# heimdall5.net
KiCad netlist of a schematic drawn in EAGLE
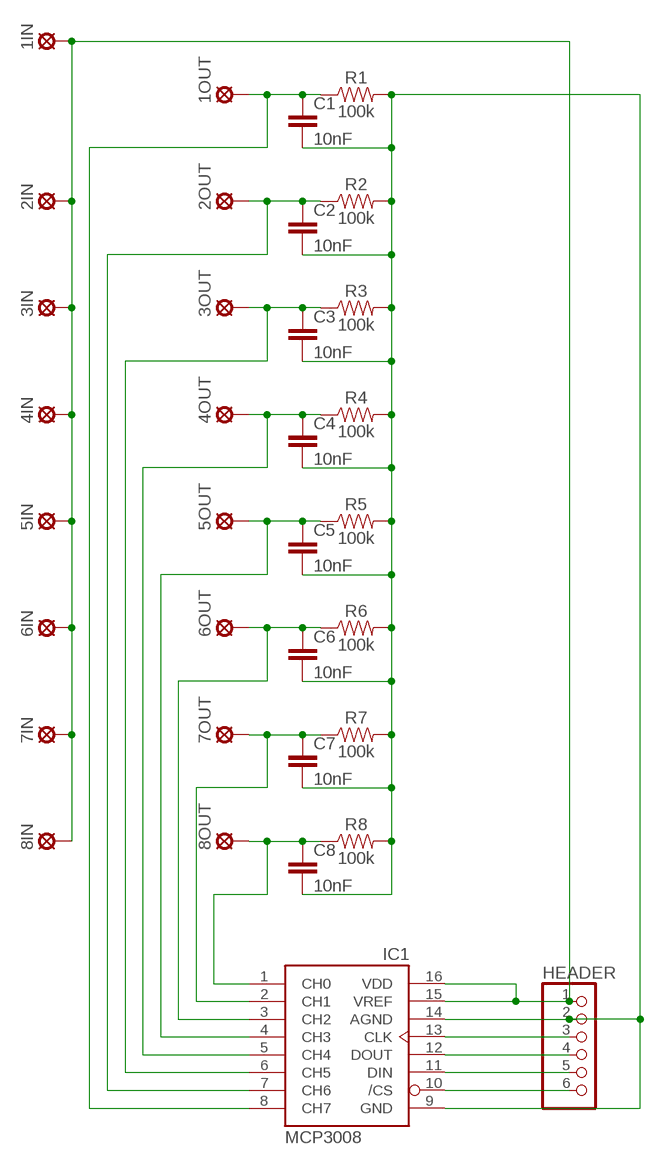
[diagram p0: schematic, sheet 1]

(export (version "E")
  (design (tool "Eeschema 10.0.6"))
  (components
    (comp (ref "1IN")
      (value "LSP11")
      (footprint "eagle-import:LSP11")
      (libsource (lib "eagle-import") (part "LSP11"))
    )
    (comp (ref "1OUT")
      (value "LSP11")
      (footprint "eagle-import:LSP11")
      (libsource (lib "eagle-import") (part "LSP11"))
    )
    (comp (ref "2IN")
      (value "LSP11")
      (footprint "eagle-import:LSP11")
      (libsource (lib "eagle-import") (part "LSP11"))
    )
    (comp (ref "2OUT")
      (value "LSP11")
      (footprint "eagle-import:LSP11")
      (libsource (lib "eagle-import") (part "LSP11"))
    )
    (comp (ref "3IN")
      (value "LSP11")
      (footprint "eagle-import:LSP11")
      (libsource (lib "eagle-import") (part "LSP11"))
    )
    (comp (ref "3OUT")
      (value "LSP11")
      (footprint "eagle-import:LSP11")
      (libsource (lib "eagle-import") (part "LSP11"))
    )
    (comp (ref "4IN")
      (value "LSP11")
      (footprint "eagle-import:LSP11")
      (libsource (lib "eagle-import") (part "LSP11"))
    )
    (comp (ref "4OUT")
      (value "LSP11")
      (footprint "eagle-import:LSP11")
      (libsource (lib "eagle-import") (part "LSP11"))
    )
    (comp (ref "5IN")
      (value "LSP11")
      (footprint "eagle-import:LSP11")
      (libsource (lib "eagle-import") (part "LSP11"))
    )
    (comp (ref "5OUT")
      (value "LSP11")
      (footprint "eagle-import:LSP11")
      (libsource (lib "eagle-import") (part "LSP11"))
    )
    (comp (ref "6IN")
      (value "LSP11")
      (footprint "eagle-import:LSP11")
      (libsource (lib "eagle-import") (part "LSP11"))
    )
    (comp (ref "6OUT")
      (value "LSP11")
      (footprint "eagle-import:LSP11")
      (libsource (lib "eagle-import") (part "LSP11"))
    )
    (comp (ref "7IN")
      (value "LSP11")
      (footprint "eagle-import:LSP11")
      (libsource (lib "eagle-import") (part "LSP11"))
    )
    (comp (ref "7OUT")
      (value "LSP11")
      (footprint "eagle-import:LSP11")
      (libsource (lib "eagle-import") (part "LSP11"))
    )
    (comp (ref "8IN")
      (value "LSP11")
      (footprint "eagle-import:LSP11")
      (libsource (lib "eagle-import") (part "LSP11"))
    )
    (comp (ref "8OUT")
      (value "LSP11")
      (footprint "eagle-import:LSP11")
      (libsource (lib "eagle-import") (part "LSP11"))
    )
    (comp (ref "C1")
      (value "10nF")
      (footprint "eagle-import:050X030_050")
      (libsource (lib "eagle-import") (part "050X030_0502"))
    )
    (comp (ref "C2")
      (value "10nF")
      (footprint "eagle-import:050X030_050")
      (libsource (lib "eagle-import") (part "050X030_0502"))
    )
    (comp (ref "C3")
      (value "10nF")
      (footprint "eagle-import:050X030_050")
      (libsource (lib "eagle-import") (part "050X030_0502"))
    )
    (comp (ref "C4")
      (value "10nF")
      (footprint "eagle-import:050X030_050")
      (libsource (lib "eagle-import") (part "050X030_0502"))
    )
    (comp (ref "C5")
      (value "10nF")
      (footprint "eagle-import:050X030_050")
      (libsource (lib "eagle-import") (part "050X030_0502"))
    )
    (comp (ref "C6")
      (value "10nF")
      (footprint "eagle-import:050X030_050")
      (libsource (lib "eagle-import") (part "050X030_0502"))
    )
    (comp (ref "C7")
      (value "10nF")
      (footprint "eagle-import:050X030_050")
      (libsource (lib "eagle-import") (part "050X030_0502"))
    )
    (comp (ref "C8")
      (value "10nF")
      (footprint "eagle-import:050X030_050")
      (libsource (lib "eagle-import") (part "050X030_0502"))
    )
    (comp (ref "HEADER")
      (value "PINHD-1X6")
      (footprint "eagle-import:1X06")
      (libsource (lib "eagle-import") (part "PINHD-1X6"))
    )
    (comp (ref "IC1")
      (value "MCP3008")
      (footprint "eagle-import:DIL16")
      (libsource (lib "eagle-import") (part "MCP3008"))
    )
    (comp (ref "R1")
      (value "100k")
      (footprint "eagle-import:AXIAL-0.3")
      (libsource (lib "eagle-import") (part "100KOHM-HORIZ-1/4W-1%"))
    )
    (comp (ref "R2")
      (value "100k")
      (footprint "eagle-import:AXIAL-0.3")
      (libsource (lib "eagle-import") (part "100KOHM-HORIZ-1/4W-1%"))
    )
    (comp (ref "R3")
      (value "100k")
      (footprint "eagle-import:AXIAL-0.3")
      (libsource (lib "eagle-import") (part "100KOHM-HORIZ-1/4W-1%"))
    )
    (comp (ref "R4")
      (value "100k")
      (footprint "eagle-import:AXIAL-0.3")
      (libsource (lib "eagle-import") (part "100KOHM-HORIZ-1/4W-1%"))
    )
    (comp (ref "R5")
      (value "100k")
      (footprint "eagle-import:AXIAL-0.3")
      (libsource (lib "eagle-import") (part "100KOHM-HORIZ-1/4W-1%"))
    )
    (comp (ref "R6")
      (value "100k")
      (footprint "eagle-import:AXIAL-0.3")
      (libsource (lib "eagle-import") (part "100KOHM-HORIZ-1/4W-1%"))
    )
    (comp (ref "R7")
      (value "100k")
      (footprint "eagle-import:AXIAL-0.3")
      (libsource (lib "eagle-import") (part "100KOHM-HORIZ-1/4W-1%"))
    )
    (comp (ref "R8")
      (value "100k")
      (footprint "eagle-import:AXIAL-0.3")
      (libsource (lib "eagle-import") (part "100KOHM-HORIZ-1/4W-1%"))
    )
  )
  (nets
    (net (code "1") (name "Net-(IC1-AGND)") (class "Default")
      (node (ref "C1") (pin "2") (pinfunction "2_2") (pintype "passive"))
      (node (ref "C2") (pin "2") (pinfunction "2_2") (pintype "passive"))
      (node (ref "C3") (pin "2") (pinfunction "2_2") (pintype "passive"))
      (node (ref "C4") (pin "2") (pinfunction "2_2") (pintype "passive"))
      (node (ref "C5") (pin "2") (pinfunction "2_2") (pintype "passive"))
      (node (ref "C6") (pin "2") (pinfunction "2_2") (pintype "passive"))
      (node (ref "C7") (pin "2") (pinfunction "2_2") (pintype "passive"))
      (node (ref "C8") (pin "2") (pinfunction "2_2") (pintype "passive"))
      (node (ref "HEADER") (pin "2") (pinfunction "2_2") (pintype "passive"))
      (node (ref "IC1") (pin "14") (pinfunction "AGND_14") (pintype "power_in"))
      (node (ref "IC1") (pin "9") (pinfunction "GND_9") (pintype "power_in"))
      (node (ref "R1") (pin "P$2") (pinfunction "2_P$2") (pintype "passive"))
      (node (ref "R2") (pin "P$2") (pinfunction "2_P$2") (pintype "passive"))
      (node (ref "R3") (pin "P$2") (pinfunction "2_P$2") (pintype "passive"))
      (node (ref "R4") (pin "P$2") (pinfunction "2_P$2") (pintype "passive"))
      (node (ref "R5") (pin "P$2") (pinfunction "2_P$2") (pintype "passive"))
      (node (ref "R6") (pin "P$2") (pinfunction "2_P$2") (pintype "passive"))
      (node (ref "R7") (pin "P$2") (pinfunction "2_P$2") (pintype "passive"))
      (node (ref "R8") (pin "P$2") (pinfunction "2_P$2") (pintype "passive"))
    )
    (net (code "2") (name "Net-(IC1-CH0)") (class "Default")
      (node (ref "8OUT") (pin "MP") (pinfunction "MP_MP") (pintype "passive"))
      (node (ref "C8") (pin "1") (pinfunction "1_1") (pintype "passive"))
      (node (ref "IC1") (pin "1") (pinfunction "CH0_1") (pintype "input"))
      (node (ref "R8") (pin "P$1") (pinfunction "1_P$1") (pintype "passive"))
    )
    (net (code "3") (name "Net-(IC1-CH1)") (class "Default")
      (node (ref "7OUT") (pin "MP") (pinfunction "MP_MP") (pintype "passive"))
      (node (ref "C7") (pin "1") (pinfunction "1_1") (pintype "passive"))
      (node (ref "IC1") (pin "2") (pinfunction "CH1_2") (pintype "input"))
      (node (ref "R7") (pin "P$1") (pinfunction "1_P$1") (pintype "passive"))
    )
    (net (code "4") (name "Net-(IC1-CH2)") (class "Default")
      (node (ref "6OUT") (pin "MP") (pinfunction "MP_MP") (pintype "passive"))
      (node (ref "C6") (pin "1") (pinfunction "1_1") (pintype "passive"))
      (node (ref "IC1") (pin "3") (pinfunction "CH2_3") (pintype "input"))
      (node (ref "R6") (pin "P$1") (pinfunction "1_P$1") (pintype "passive"))
    )
    (net (code "5") (name "Net-(IC1-CH3)") (class "Default")
      (node (ref "5OUT") (pin "MP") (pinfunction "MP_MP") (pintype "passive"))
      (node (ref "C5") (pin "1") (pinfunction "1_1") (pintype "passive"))
      (node (ref "IC1") (pin "4") (pinfunction "CH3_4") (pintype "input"))
      (node (ref "R5") (pin "P$1") (pinfunction "1_P$1") (pintype "passive"))
    )
    (net (code "6") (name "Net-(IC1-CH4)") (class "Default")
      (node (ref "4OUT") (pin "MP") (pinfunction "MP_MP") (pintype "passive"))
      (node (ref "C4") (pin "1") (pinfunction "1_1") (pintype "passive"))
      (node (ref "IC1") (pin "5") (pinfunction "CH4_5") (pintype "input"))
      (node (ref "R4") (pin "P$1") (pinfunction "1_P$1") (pintype "passive"))
    )
    (net (code "7") (name "Net-(IC1-CH5)") (class "Default")
      (node (ref "3OUT") (pin "MP") (pinfunction "MP_MP") (pintype "passive"))
      (node (ref "C3") (pin "1") (pinfunction "1_1") (pintype "passive"))
      (node (ref "IC1") (pin "6") (pinfunction "CH5_6") (pintype "input"))
      (node (ref "R3") (pin "P$1") (pinfunction "1_P$1") (pintype "passive"))
    )
    (net (code "8") (name "Net-(IC1-CH6)") (class "Default")
      (node (ref "2OUT") (pin "MP") (pinfunction "MP_MP") (pintype "passive"))
      (node (ref "C2") (pin "1") (pinfunction "1_1") (pintype "passive"))
      (node (ref "IC1") (pin "7") (pinfunction "CH6_7") (pintype "input"))
      (node (ref "R2") (pin "P$1") (pinfunction "1_P$1") (pintype "passive"))
    )
    (net (code "9") (name "Net-(IC1-CH7)") (class "Default")
      (node (ref "1OUT") (pin "MP") (pinfunction "MP_MP") (pintype "passive"))
      (node (ref "C1") (pin "1") (pinfunction "1_1") (pintype "passive"))
      (node (ref "IC1") (pin "8") (pinfunction "CH7_8") (pintype "input"))
      (node (ref "R1") (pin "P$1") (pinfunction "1_P$1") (pintype "passive"))
    )
    (net (code "10") (name "Net-(IC1-CLK)") (class "Default")
      (node (ref "HEADER") (pin "3") (pinfunction "3_3") (pintype "passive"))
      (node (ref "IC1") (pin "13") (pinfunction "CLK_13") (pintype "input"))
    )
    (net (code "11") (name "Net-(IC1-DIN)") (class "Default")
      (node (ref "HEADER") (pin "5") (pinfunction "5_5") (pintype "passive"))
      (node (ref "IC1") (pin "11") (pinfunction "DIN_11") (pintype "input"))
    )
    (net (code "12") (name "Net-(IC1-DOUT)") (class "Default")
      (node (ref "HEADER") (pin "4") (pinfunction "4_4") (pintype "passive"))
      (node (ref "IC1") (pin "12") (pinfunction "DOUT_12") (pintype "output"))
    )
    (net (code "13") (name "Net-(IC1-VDD)") (class "Default")
      (node (ref "1IN") (pin "MP") (pinfunction "MP_MP") (pintype "passive"))
      (node (ref "2IN") (pin "MP") (pinfunction "MP_MP") (pintype "passive"))
      (node (ref "3IN") (pin "MP") (pinfunction "MP_MP") (pintype "passive"))
      (node (ref "4IN") (pin "MP") (pinfunction "MP_MP") (pintype "passive"))
      (node (ref "5IN") (pin "MP") (pinfunction "MP_MP") (pintype "passive"))
      (node (ref "6IN") (pin "MP") (pinfunction "MP_MP") (pintype "passive"))
      (node (ref "7IN") (pin "MP") (pinfunction "MP_MP") (pintype "passive"))
      (node (ref "8IN") (pin "MP") (pinfunction "MP_MP") (pintype "passive"))
      (node (ref "HEADER") (pin "1") (pinfunction "1_1") (pintype "passive"))
      (node (ref "IC1") (pin "15") (pinfunction "VREF_15") (pintype "input"))
      (node (ref "IC1") (pin "16") (pinfunction "VDD_16") (pintype "power_in"))
    )
    (net (code "14") (name "Net-(IC1-{slash}CS)") (class "Default")
      (node (ref "HEADER") (pin "6") (pinfunction "6_6") (pintype "passive"))
      (node (ref "IC1") (pin "10") (pinfunction "/CS_10") (pintype "input"))
    )
  )
)
